# UpStream.net
KiCad netlist of a schematic drawn in Altium Designer
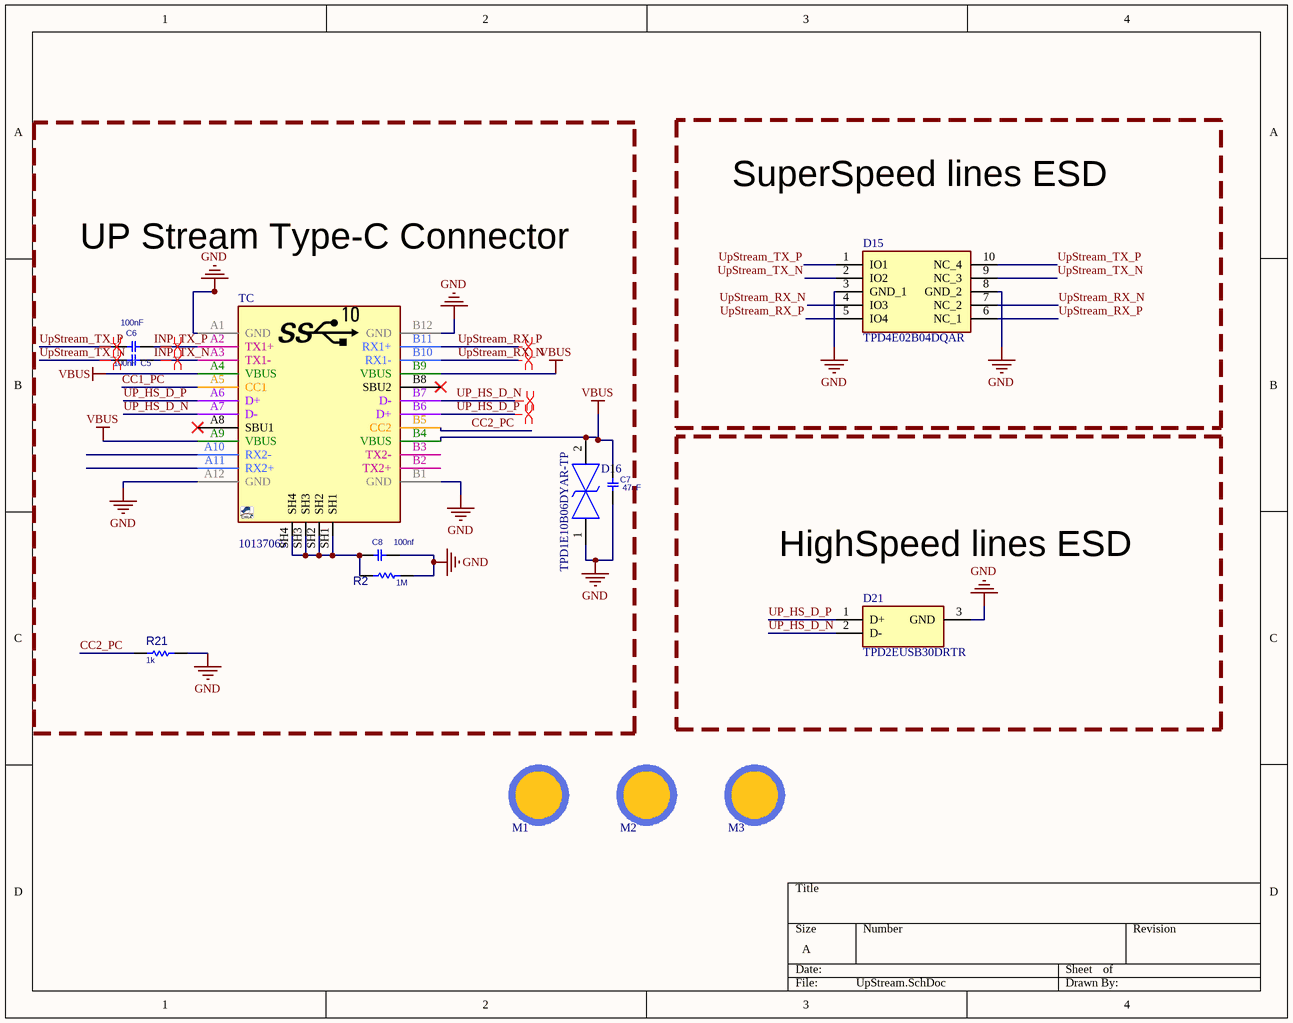
[diagram p0: UpStream.SchDoc]

(export (version "E")
  (design (tool "Eeschema 10.0.6"))
  (components
    (comp (ref "C5")
      (value "100nF")
      (footprint "C0402")
      (libsource (lib "passive_smd") (part "CAP_SMD_MLCC_0402"))
    )
    (comp (ref "C6")
      (value "100nF")
      (footprint "C0402")
      (libsource (lib "passive_smd") (part "CAP_SMD_MLCC_0402"))
    )
    (comp (ref "C7")
      (value "47uF")
      (footprint "C0805")
      (libsource (lib "passive_smd") (part "CAP_SMD_MLCC_0805"))
    )
    (comp (ref "C8")
      (value "100nf")
      (footprint "C1812")
      (description "+1kv 100nf")
      (libsource (lib "passive_smd") (part "CAP_SMD_MLCC_1812"))
    )
    (comp (ref "D15")
      (value "TPD4E02B04DQAR")
      (footprint "SamacSys:DQA(R-PUSON-N10)")
      (description "Diode")
      (fields (field (name "MOUSER PART NUMBER") "595-TPD4E02B04DQAR"))
      (libsource (lib "*") (part "TPD4E02B04DQAR"))
    )
    (comp (ref "D16")
      (value "TPD1E10B06DYAR-TP")
      (footprint "SamacSys:SODFL1608X77N")
      (description "TVS Diode (Bi-directional)")
      (fields
        (field (name "MANUFACTURER_PART_NUMBER") "TPD1E10B06DYARQ1")
        (field (name "MOUSER PART NUMBER") "595-TPD1E10B06DYARQ1")
      )
      (libsource (lib "*") (part "TPD1E10B06DYARQ1"))
    )
    (comp (ref "D21")
      (value "TPD2EUSB30DRTR")
      (footprint "SamacSys:SOTFL35P100X50-3N")
      (description "TPD2EUSB30ADRTR")
      (fields (field (name "MOUSER PART NUMBER") "595-TPD2EUSB30DRTR"))
      (libsource (lib "*") (part "TPD2EUSB30DRTR"))
    )
    (comp (ref "M1")
      (value "DNP/MH")
      (footprint "PSPMH2")
      (description "Plastic Spacer mouting, Hole 2mm")
      (libsource (lib "mech_mountingHole") (part "PSPMH2"))
    )
    (comp (ref "M2")
      (value "DNP/MH")
      (footprint "PSPMH2")
      (description "Plastic Spacer mouting, Hole 2mm")
      (libsource (lib "mech_mountingHole") (part "PSPMH2"))
    )
    (comp (ref "M3")
      (value "DNP/MH")
      (footprint "PSPMH2")
      (description "Plastic Spacer mouting, Hole 2mm")
      (libsource (lib "mech_mountingHole") (part "PSPMH2"))
    )
    (comp (ref "R2")
      (value "1M")
      (footprint "R0805")
      (description "RESISTOR, SMD")
      (libsource (lib "passive_smd") (part "RES_SMD_0402"))
    )
    (comp (ref "R21")
      (value "1k")
      (footprint "R0402")
      (description "RESISTOR, SMD")
      (libsource (lib "passive_smd") (part "RES_SMD_0402"))
    )
    (comp (ref "TC")
      (value "10137065")
      (footprint "USBC_HYB_UJ31CHG2SMT")
      (description "CONN, USB, Type C, USB 3.1 Gen 1, Right-Angle, SMD")
      (fields (field (name "MANF") "Amphenol") (field (name "MANF_P#") "10137065-00021LF"))
      (libsource (lib "conn_usbc") (part "CONN_USBC_SMD_10137065"))
    )
  )
  (nets
    (net (code "1") (name "/CC1_PC") (class "Default")
      (node (ref "TC") (pin "A5") (pinfunction "CC1_A5") (pintype "passive"))
    )
    (net (code "2") (name "/CC2_PC") (class "Default")
      (node (ref "R21") (pin "1") (pinfunction "1_1") (pintype "passive"))
      (node (ref "TC") (pin "B5") (pinfunction "CC2_B5") (pintype "passive"))
    )
    (net (code "3") (name "/INP_TX_N") (class "Default")
      (node (ref "C5") (pin "2") (pinfunction "2_2") (pintype "passive"))
      (node (ref "TC") (pin "A3") (pinfunction "TX1-_A3") (pintype "passive"))
    )
    (net (code "4") (name "/INP_TX_P") (class "Default")
      (node (ref "C6") (pin "2") (pinfunction "2_2") (pintype "passive"))
      (node (ref "TC") (pin "A2") (pinfunction "TX1+_A2") (pintype "passive"))
    )
    (net (code "5") (name "/UP_HS_D_N") (class "Default")
      (node (ref "D21") (pin "2") (pinfunction "D-_2") (pintype "passive"))
      (node (ref "TC") (pin "A7") (pinfunction "D-_A7") (pintype "passive"))
      (node (ref "TC") (pin "B7") (pinfunction "D-_B7") (pintype "passive"))
    )
    (net (code "6") (name "/UP_HS_D_P") (class "Default")
      (node (ref "D21") (pin "1") (pinfunction "D+_1") (pintype "passive"))
      (node (ref "TC") (pin "A6") (pinfunction "D+_A6") (pintype "passive"))
      (node (ref "TC") (pin "B6") (pinfunction "D+_B6") (pintype "passive"))
    )
    (net (code "7") (name "/UpStream_RX_N") (class "Default")
      (node (ref "D15") (pin "4") (pinfunction "IO3_4") (pintype "passive"))
      (node (ref "D15") (pin "7") (pinfunction "NC_2_7") (pintype "passive"))
      (node (ref "TC") (pin "B10") (pinfunction "RX1-_B10") (pintype "passive"))
    )
    (net (code "8") (name "/UpStream_RX_P") (class "Default")
      (node (ref "D15") (pin "5") (pinfunction "IO4_5") (pintype "passive"))
      (node (ref "D15") (pin "6") (pinfunction "NC_1_6") (pintype "passive"))
      (node (ref "TC") (pin "B11") (pinfunction "RX1+_B11") (pintype "passive"))
    )
    (net (code "9") (name "/UpStream_TX_N") (class "Default")
      (node (ref "C5") (pin "1") (pinfunction "1_1") (pintype "passive"))
      (node (ref "D15") (pin "2") (pinfunction "IO2_2") (pintype "passive"))
      (node (ref "D15") (pin "9") (pinfunction "NC_3_9") (pintype "passive"))
    )
    (net (code "10") (name "/UpStream_TX_P") (class "Default")
      (node (ref "C6") (pin "1") (pinfunction "1_1") (pintype "passive"))
      (node (ref "D15") (pin "1") (pinfunction "IO1_1") (pintype "passive"))
      (node (ref "D15") (pin "10") (pinfunction "NC_4_10") (pintype "passive"))
    )
    (net (code "11") (name "GND") (class "Default")
      (node (ref "C7") (pin "1") (pinfunction "1_1") (pintype "passive"))
      (node (ref "C8") (pin "2") (pinfunction "2_2") (pintype "passive"))
      (node (ref "D15") (pin "3") (pinfunction "GND_1_3") (pintype "passive"))
      (node (ref "D15") (pin "8") (pinfunction "GND_2_8") (pintype "passive"))
      (node (ref "D16") (pin "1") (pinfunction "1_1") (pintype "passive"))
      (node (ref "D21") (pin "3") (pinfunction "GND_3") (pintype "passive"))
      (node (ref "R2") (pin "1") (pinfunction "1_1") (pintype "passive"))
      (node (ref "R21") (pin "2") (pinfunction "2_2") (pintype "passive"))
      (node (ref "TC") (pin "A1") (pinfunction "GND_A1") (pintype "passive"))
      (node (ref "TC") (pin "A12") (pinfunction "GND_A12") (pintype "passive"))
      (node (ref "TC") (pin "B1") (pinfunction "GND_B1") (pintype "passive"))
      (node (ref "TC") (pin "B12") (pinfunction "GND_B12") (pintype "passive"))
    )
    (net (code "12") (name "Net-(C8-Pad1)") (class "Default")
      (node (ref "C8") (pin "1") (pinfunction "1_1") (pintype "passive"))
      (node (ref "R2") (pin "2") (pinfunction "2_2") (pintype "passive"))
      (node (ref "TC") (pin "SH1") (pinfunction "SH1_SH1") (pintype "passive"))
      (node (ref "TC") (pin "SH2") (pinfunction "SH2_SH2") (pintype "passive"))
      (node (ref "TC") (pin "SH3") (pinfunction "SH3_SH3") (pintype "passive"))
      (node (ref "TC") (pin "SH4") (pinfunction "SH4_SH4") (pintype "passive"))
    )
    (net (code "13") (name "VBUS") (class "Default")
      (node (ref "C7") (pin "2") (pinfunction "2_2") (pintype "passive"))
      (node (ref "D16") (pin "2") (pinfunction "2_2") (pintype "passive"))
      (node (ref "TC") (pin "A4") (pinfunction "VBUS_A4") (pintype "passive"))
      (node (ref "TC") (pin "A9") (pinfunction "VBUS_A9") (pintype "passive"))
      (node (ref "TC") (pin "B4") (pinfunction "VBUS_B4") (pintype "passive"))
      (node (ref "TC") (pin "B9") (pinfunction "VBUS_B9") (pintype "passive"))
    )
    (net (code "14") (name "unconnected-(TC-RX2+-PadA11)") (class "Default")
      (node (ref "TC") (pin "A11") (pinfunction "RX2+_A11") (pintype "passive"))
    )
    (net (code "15") (name "unconnected-(TC-RX2--PadA10)") (class "Default")
      (node (ref "TC") (pin "A10") (pinfunction "RX2-_A10") (pintype "passive"))
    )
    (net (code "16") (name "unconnected-(TC-SBU1-PadA8)") (class "Default")
      (node (ref "TC") (pin "A8") (pinfunction "SBU1_A8") (pintype "passive+no_connect"))
    )
    (net (code "17") (name "unconnected-(TC-SBU2-PadB8)") (class "Default")
      (node (ref "TC") (pin "B8") (pinfunction "SBU2_B8") (pintype "passive+no_connect"))
    )
    (net (code "18") (name "unconnected-(TC-TX2+-PadB2)") (class "Default")
      (node (ref "TC") (pin "B2") (pinfunction "TX2+_B2") (pintype "passive"))
    )
    (net (code "19") (name "unconnected-(TC-TX2--PadB3)") (class "Default")
      (node (ref "TC") (pin "B3") (pinfunction "TX2-_B3") (pintype "passive"))
    )
  )
)
